# guitar_tuner.net
KiCad netlist of a schematic drawn in Altium Designer
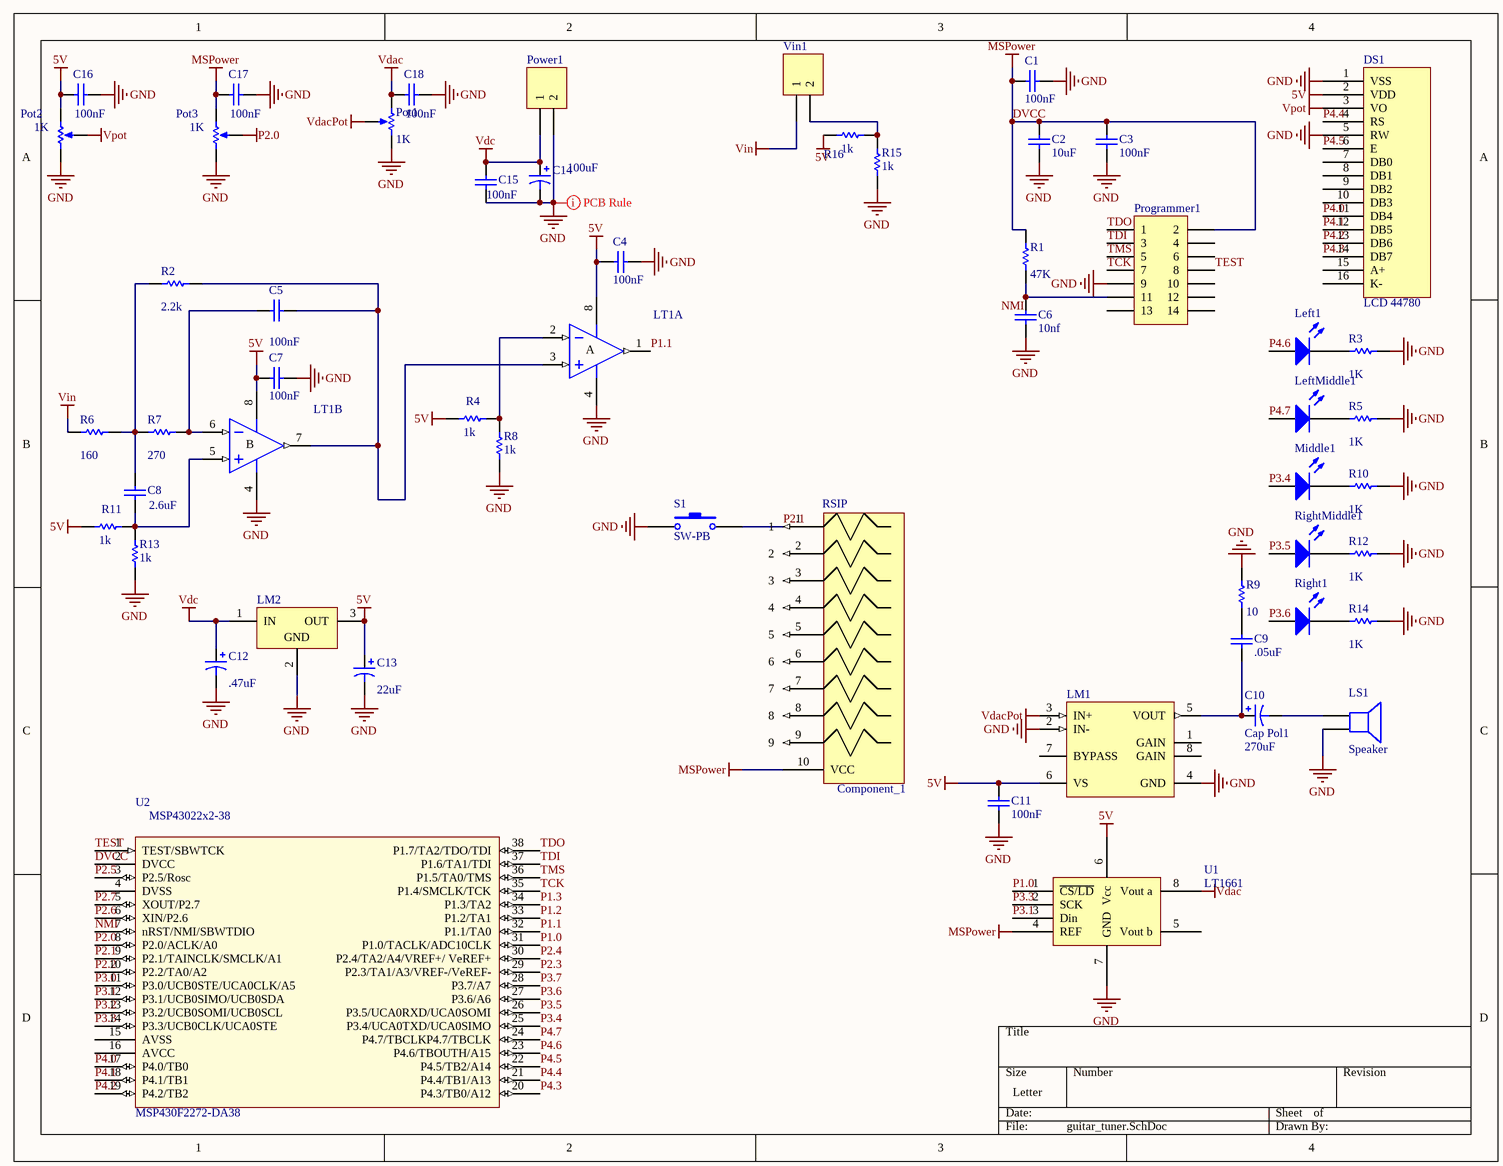
[diagram p0: guitar_tuner.SchDoc]

(export (version "E")
  (design (tool "Eeschema 10.0.6"))
  (components
    (comp (ref "C1")
      (value "100nF")
      (footprint "RAD-0.1")
      (description "Capacitor")
      (fields (field (name "Comment") "Cap") (field (name "PUBLISHER") "Altium Limited"))
      (libsource (lib "Miscellaneous Devices") (part "Cap"))
    )
    (comp (ref "C2")
      (value "10uF")
      (footprint "RAD-0.1")
      (description "Capacitor")
      (fields (field (name "Comment") "Cap") (field (name "PUBLISHER") "Altium Limited"))
      (libsource (lib "Miscellaneous Devices") (part "Cap"))
    )
    (comp (ref "C3")
      (value "100nF")
      (footprint "RAD-0.1")
      (description "Capacitor")
      (fields (field (name "Comment") "Cap") (field (name "PUBLISHER") "Altium Limited"))
      (libsource (lib "Miscellaneous Devices") (part "Cap"))
    )
    (comp (ref "C4")
      (value "100nF")
      (footprint "RAD-0.1")
      (description "Capacitor")
      (fields (field (name "Comment") "Cap") (field (name "PUBLISHER") "Altium Limited"))
      (libsource (lib "Miscellaneous Devices") (part "Cap"))
    )
    (comp (ref "C5")
      (value "100nF")
      (footprint "RAD-0.1")
      (description "Capacitor")
      (fields (field (name "Comment") "Cap") (field (name "PUBLISHER") "Altium Limited"))
      (libsource (lib "Miscellaneous Devices") (part "Cap"))
    )
    (comp (ref "C6")
      (value "10nf")
      (footprint "RAD-0.1")
      (description "Capacitor")
      (fields (field (name "Comment") "Cap") (field (name "PUBLISHER") "Altium Limited"))
      (libsource (lib "Miscellaneous Devices") (part "Cap"))
    )
    (comp (ref "C7")
      (value "100nF")
      (footprint "RAD-0.1")
      (description "Capacitor")
      (fields (field (name "Comment") "Cap") (field (name "PUBLISHER") "Altium Limited"))
      (libsource (lib "Miscellaneous Devices") (part "Cap"))
    )
    (comp (ref "C8")
      (value "2.6uF")
      (footprint "RAD-0.1")
      (description "Capacitor")
      (fields (field (name "Comment") "Cap") (field (name "PUBLISHER") "Altium Limited"))
      (libsource (lib "Miscellaneous Devices") (part "Cap"))
    )
    (comp (ref "C9")
      (value ".05uF")
      (footprint "RAD-0.1")
      (description "Capacitor")
      (fields (field (name "Comment") "Cap") (field (name "PUBLISHER") "Altium Limited"))
      (libsource (lib "Miscellaneous Devices") (part "Cap"))
    )
    (comp (ref "C10")
      (value "Cap Pol1")
      (footprint "CAPR5-4X5")
      (description "Polarized Capacitor (Radial)")
      (fields (field (name "ALTIUM_VALUE") "270uF") (field (name "PUBLISHER") "Altium Limited"))
      (libsource (lib "Miscellaneous Devices") (part "Cap Pol1"))
    )
    (comp (ref "C11")
      (value "100nF")
      (footprint "RAD-0.1")
      (description "Capacitor")
      (fields (field (name "Comment") "Cap") (field (name "PUBLISHER") "Altium Limited"))
      (libsource (lib "Miscellaneous Devices") (part "Cap"))
    )
    (comp (ref "C12")
      (value ".47uF")
      (footprint "CAPR5-4X5")
      (description "Polarized Capacitor (Radial)")
      (fields (field (name "Comment") "Cap Pol1") (field (name "PUBLISHER") "Altium Limited"))
      (libsource (lib "Miscellaneous Devices") (part "Cap Pol1"))
    )
    (comp (ref "C13")
      (value "22uF")
      (footprint "CAPR5-4X5")
      (description "Polarized Capacitor (Radial)")
      (fields (field (name "Comment") "Cap Pol1") (field (name "PUBLISHER") "Altium Limited"))
      (libsource (lib "Miscellaneous Devices") (part "Cap Pol1"))
    )
    (comp (ref "C14")
      (value "100uF")
      (footprint "CAPR5-4X5")
      (description "Polarized Capacitor (Radial)")
      (fields (field (name "Comment") "Cap Pol1") (field (name "PUBLISHER") "Altium Limited"))
      (libsource (lib "Miscellaneous Devices") (part "Cap Pol1"))
    )
    (comp (ref "C15")
      (value "100nF")
      (footprint "RAD-0.1")
      (description "Capacitor")
      (fields (field (name "Comment") "Cap") (field (name "PUBLISHER") "Altium Limited"))
      (libsource (lib "Miscellaneous Devices") (part "Cap"))
    )
    (comp (ref "C16")
      (value "100nF")
      (footprint "RAD-0.1")
      (description "Capacitor")
      (fields (field (name "Comment") "Cap") (field (name "PUBLISHER") "Altium Limited"))
      (libsource (lib "Miscellaneous Devices") (part "Cap"))
    )
    (comp (ref "C17")
      (value "100nF")
      (footprint "RAD-0.1")
      (description "Capacitor")
      (fields (field (name "Comment") "Cap") (field (name "PUBLISHER") "Altium Limited"))
      (libsource (lib "Miscellaneous Devices") (part "Cap"))
    )
    (comp (ref "C18")
      (value "100nF")
      (footprint "RAD-0.1")
      (description "Capacitor")
      (fields (field (name "Comment") "Cap") (field (name "PUBLISHER") "Altium Limited"))
      (libsource (lib "Miscellaneous Devices") (part "Cap"))
    )
    (comp (ref "DS1")
      (value "LCD 44780")
      (footprint "OLED 16x2")
      (libsource (lib "ECE Lib") (part "LCD 44780"))
    )
    (comp (ref "Left1")
      (value "LED1")
      (footprint "LED-1")
      (description "Typical RED GaAs LED")
      (fields (field (name "PUBLISHER") "Altium Limited"))
      (libsource (lib "Miscellaneous Devices") (part "LED1"))
    )
    (comp (ref "LeftMiddle1")
      (value "LED1")
      (footprint "LED-1")
      (description "Typical RED GaAs LED")
      (fields (field (name "PUBLISHER") "Altium Limited"))
      (libsource (lib "Miscellaneous Devices") (part "LED1"))
    )
    (comp (ref "LM1")
      (value "LM386N-1")
      (footprint "N08E")
      (description "Low Voltage Audio Power Amplifier, 8-pin MDIP")
      (fields
        (field (name "MANUFACTURER") "National Semiconductor")
        (field (name "PUBLISHER") "Altium Limited")
      )
      (libsource (lib "NSC Audio") (part "LM386N-1"))
    )
    (comp (ref "LM2")
      (value "LM330KC")
      (footprint "KC03")
      (description "3-Terminal Positive Regulator")
      (fields (field (name "PUBLISHER") "Altium Limited"))
      (libsource (lib "TI Power Mgt Voltage Regulator") (part "LM330KC"))
    )
    (comp (ref "LS1")
      (value "Speaker")
      (footprint "PIN2")
      (description "Loudspeaker")
      (fields (field (name "PUBLISHER") "Altium Limited"))
      (libsource (lib "Miscellaneous Devices") (part "Speaker"))
    )
    (comp (ref "LT1")
      (value "LF353P")
      (footprint "P008")
      (description "Dual Operational Amplifier")
      (fields (field (name "PUBLISHER") "Altium Limited"))
      (libsource (lib "TI Operational Amplifier") (part "LF353P"))
    )
    (comp (ref "Middle1")
      (value "LED1")
      (footprint "LED-1")
      (description "Typical RED GaAs LED")
      (fields (field (name "PUBLISHER") "Altium Limited"))
      (libsource (lib "Miscellaneous Devices") (part "LED1"))
    )
    (comp (ref "Pot1")
      (value "1K")
      (footprint "VR5")
      (description "Potentiometer")
      (fields (field (name "Comment") "RPot") (field (name "PUBLISHER") "Altium Limited"))
      (libsource (lib "Miscellaneous Devices") (part "RPot"))
    )
    (comp (ref "Pot2")
      (value "1K")
      (footprint "VR5")
      (description "Potentiometer")
      (fields (field (name "Comment") "RPot") (field (name "PUBLISHER") "Altium Limited"))
      (libsource (lib "") (part "RPot_1"))
    )
    (comp (ref "Pot3")
      (value "1K")
      (footprint "VR5")
      (description "Potentiometer")
      (fields (field (name "Comment") "RPot") (field (name "PUBLISHER") "Altium Limited"))
      (libsource (lib "") (part "RPot_2"))
    )
    (comp (ref "Power1")
      (value "Power")
      (footprint "HDR1X2")
      (description "Header, 2-Pin")
      (fields (field (name "PUBLISHER") "Altium Limited"))
      (libsource (lib "Miscellaneous Connectors") (part "Header 2"))
    )
    (comp (ref "Programmer1")
      (value "Header 7X2")
      (footprint "HDR2X7")
      (description "Header, 7-Pin, Dual row")
      (fields (field (name "PUBLISHER") "Altium Limited"))
      (libsource (lib "Miscellaneous Connectors") (part "Header 7X2"))
    )
    (comp (ref "R1")
      (value "47K")
      (footprint "AXIAL-0.3")
      (description "Resistor")
      (fields (field (name "Comment") "Res1") (field (name "PUBLISHER") "Altium Limited"))
      (libsource (lib "Miscellaneous Devices") (part "Res1"))
    )
    (comp (ref "R2")
      (value "2.2k")
      (footprint "AXIAL-0.3")
      (description "Resistor")
      (fields (field (name "Comment") "Res1") (field (name "PUBLISHER") "Altium Limited"))
      (libsource (lib "Miscellaneous Devices") (part "Res1"))
    )
    (comp (ref "R3")
      (value "1K")
      (footprint "AXIAL-0.3")
      (description "Resistor")
      (fields (field (name "Comment") "Res1") (field (name "PUBLISHER") "Altium Limited"))
      (libsource (lib "Miscellaneous Devices") (part "Res1"))
    )
    (comp (ref "R4")
      (value "1k")
      (footprint "AXIAL-0.3")
      (description "Resistor")
      (fields (field (name "Comment") "Res1") (field (name "PUBLISHER") "Altium Limited"))
      (libsource (lib "Miscellaneous Devices") (part "Res1"))
    )
    (comp (ref "R5")
      (value "1K")
      (footprint "AXIAL-0.3")
      (description "Resistor")
      (fields (field (name "Comment") "Res1") (field (name "PUBLISHER") "Altium Limited"))
      (libsource (lib "Miscellaneous Devices") (part "Res1"))
    )
    (comp (ref "R6")
      (value "160")
      (footprint "AXIAL-0.3")
      (description "Resistor")
      (fields (field (name "Comment") "Res1") (field (name "PUBLISHER") "Altium Limited"))
      (libsource (lib "Miscellaneous Devices") (part "Res1"))
    )
    (comp (ref "R7")
      (value "270")
      (footprint "AXIAL-0.3")
      (description "Resistor")
      (fields (field (name "Comment") "Res1") (field (name "PUBLISHER") "Altium Limited"))
      (libsource (lib "Miscellaneous Devices") (part "Res1"))
    )
    (comp (ref "R8")
      (value "1k")
      (footprint "AXIAL-0.3")
      (description "Resistor")
      (fields (field (name "Comment") "Res1") (field (name "PUBLISHER") "Altium Limited"))
      (libsource (lib "Miscellaneous Devices") (part "Res1"))
    )
    (comp (ref "R9")
      (value "10")
      (footprint "AXIAL-0.3")
      (description "Resistor")
      (fields (field (name "Comment") "Res1") (field (name "PUBLISHER") "Altium Limited"))
      (libsource (lib "Miscellaneous Devices") (part "Res1"))
    )
    (comp (ref "R10")
      (value "1K")
      (footprint "AXIAL-0.3")
      (description "Resistor")
      (fields (field (name "Comment") "Res1") (field (name "PUBLISHER") "Altium Limited"))
      (libsource (lib "Miscellaneous Devices") (part "Res1"))
    )
    (comp (ref "R11")
      (value "1k")
      (footprint "AXIAL-0.3")
      (description "Resistor")
      (fields (field (name "Comment") "Res1") (field (name "PUBLISHER") "Altium Limited"))
      (libsource (lib "Miscellaneous Devices") (part "Res1"))
    )
    (comp (ref "R12")
      (value "1K")
      (footprint "AXIAL-0.3")
      (description "Resistor")
      (fields (field (name "Comment") "Res1") (field (name "PUBLISHER") "Altium Limited"))
      (libsource (lib "Miscellaneous Devices") (part "Res1"))
    )
    (comp (ref "R13")
      (value "1k")
      (footprint "AXIAL-0.3")
      (description "Resistor")
      (fields (field (name "Comment") "Res1") (field (name "PUBLISHER") "Altium Limited"))
      (libsource (lib "Miscellaneous Devices") (part "Res1"))
    )
    (comp (ref "R14")
      (value "1K")
      (footprint "AXIAL-0.3")
      (description "Resistor")
      (fields (field (name "Comment") "Res1") (field (name "PUBLISHER") "Altium Limited"))
      (libsource (lib "Miscellaneous Devices") (part "Res1"))
    )
    (comp (ref "R15")
      (value "1k")
      (footprint "AXIAL-0.3")
      (description "Resistor")
      (fields (field (name "Comment") "Res1") (field (name "PUBLISHER") "Altium Limited"))
      (libsource (lib "Miscellaneous Devices") (part "Res1"))
    )
    (comp (ref "R16")
      (value "1k")
      (footprint "AXIAL-0.3")
      (description "Resistor")
      (fields (field (name "Comment") "Res1") (field (name "PUBLISHER") "Altium Limited"))
      (libsource (lib "Miscellaneous Devices") (part "Res1"))
    )
    (comp (ref "Right1")
      (value "LED1")
      (footprint "LED-1")
      (description "Typical RED GaAs LED")
      (fields (field (name "PUBLISHER") "Altium Limited"))
      (libsource (lib "Miscellaneous Devices") (part "LED1"))
    )
    (comp (ref "RightMiddle1")
      (value "LED1")
      (footprint "LED-1")
      (description "Typical RED GaAs LED")
      (fields (field (name "PUBLISHER") "Altium Limited"))
      (libsource (lib "Miscellaneous Devices") (part "LED1"))
    )
    (comp (ref "RSIP")
      (value "Component_1")
      (footprint "LTC1661")
      (libsource (lib "Rsip") (part "Component_1"))
    )
    (comp (ref "S1")
      (value "SW-PB")
      (footprint "SW PB")
      (description "DIGIKEY SW400-ND")
      (fields (field (name "PUBLISHER") "Altium Limited"))
      (libsource (lib "ECE Lib") (part "SW-PB"))
    )
    (comp (ref "U1") (value "LT1661") (footprint "DIP-8") (libsource (lib "ECE Lib") (part "LT1661")))
    (comp (ref "U2")
      (value "MSP430F2272-DA38")
      (footprint "DIP38")
      (libsource (lib "ECE Lib") (part "MSP430F22x2-DA38"))
    )
    (comp (ref "Vin1")
      (value "GuitarIn")
      (footprint "HDR1X2")
      (description "Header, 2-Pin")
      (fields (field (name "PUBLISHER") "Altium Limited"))
      (libsource (lib "Miscellaneous Connectors") (part "Header 2"))
    )
  )
  (nets
    (net (code "1") (name "/NMI") (class "Default")
      (node (ref "C6") (pin "1") (pinfunction "1_1") (pintype "passive"))
      (node (ref "Programmer1") (pin "11") (pinfunction "11_11") (pintype "passive"))
      (node (ref "R1") (pin "1") (pinfunction "1_1") (pintype "passive"))
      (node (ref "U2") (pin "7") (pinfunction "nRST/NMI/SBWTDIO_7") (pintype "bidirectional"))
    )
    (net (code "2") (name "/P1.0") (class "Default")
      (node (ref "U1") (pin "1") (pinfunction "~{CS/LD}_1") (pintype "passive"))
      (node (ref "U2") (pin "31") (pinfunction "P1.0/TACLK/ADC10CLK_31") (pintype "bidirectional"))
    )
    (net (code "3") (name "/P1.1") (class "Default")
      (node (ref "LT1") (pin "1") (pinfunction "OUT_1") (pintype "output"))
      (node (ref "U2") (pin "32") (pinfunction "P1.1/TA0_32") (pintype "bidirectional"))
    )
    (net (code "4") (name "/P1.2") (class "Default")
      (node (ref "U2") (pin "33") (pinfunction "P1.2/TA1_33") (pintype "bidirectional"))
    )
    (net (code "5") (name "/P1.3") (class "Default")
      (node (ref "U2") (pin "34") (pinfunction "P1.3/TA2_34") (pintype "bidirectional"))
    )
    (net (code "6") (name "/P2.1") (class "Default")
      (node (ref "S1") (pin "2") (pinfunction "2_2") (pintype "passive"))
      (node (ref "U2") (pin "9") (pinfunction "P2.1/TAINCLK/SMCLK/A1_9") (pintype "bidirectional"))
    )
    (net (code "7") (name "/P2.2") (class "Default")
      (node (ref "U2") (pin "10") (pinfunction "P2.2/TA0/A2_10") (pintype "bidirectional"))
    )
    (net (code "8") (name "/P2.3") (class "Default")
      (node (ref "U2") (pin "29") (pinfunction "P2.3/TA1/A3/VREF-/VeREF-_29") (pintype "bidirectional"))
    )
    (net (code "9") (name "/P2.4") (class "Default")
      (node (ref "U2") (pin "30") (pinfunction "P2.4/TA2/A4/VREF+/_VeREF+_30") (pintype "bidirectional"))
    )
    (net (code "10") (name "/P2.5") (class "Default")
      (node (ref "U2") (pin "3") (pinfunction "P2.5/Rosc_3") (pintype "bidirectional"))
    )
    (net (code "11") (name "/P2.6") (class "Default")
      (node (ref "U2") (pin "6") (pinfunction "XIN/P2.6_6") (pintype "bidirectional"))
    )
    (net (code "12") (name "/P2.7") (class "Default")
      (node (ref "U2") (pin "5") (pinfunction "XOUT/P2.7_5") (pintype "bidirectional"))
    )
    (net (code "13") (name "/P3.0") (class "Default")
      (node (ref "U2") (pin "11") (pinfunction "P3.0/UCB0STE/UCA0CLK/A5_11") (pintype "bidirectional"))
    )
    (net (code "14") (name "/P3.1") (class "Default")
      (node (ref "U1") (pin "3") (pinfunction "Din_3") (pintype "passive"))
      (node (ref "U2") (pin "12") (pinfunction "P3.1/UCB0SIMO/UCB0SDA_12") (pintype "bidirectional"))
    )
    (net (code "15") (name "/P3.2") (class "Default")
      (node (ref "U2") (pin "13") (pinfunction "P3.2/UCB0SOMI/UCB0SCL_13") (pintype "bidirectional"))
    )
    (net (code "16") (name "/P3.3") (class "Default")
      (node (ref "U1") (pin "2") (pinfunction "SCK_2") (pintype "passive"))
      (node (ref "U2") (pin "14") (pinfunction "P3.3/UCB0CLK/UCA0STE_14") (pintype "bidirectional"))
    )
    (net (code "17") (name "/P3.4") (class "Default")
      (node (ref "Middle1") (pin "1") (pinfunction "A_1") (pintype "passive"))
      (node (ref "U2") (pin "25") (pinfunction "P3.4/UCA0TXD/UCA0SIMO_25") (pintype "bidirectional"))
    )
    (net (code "18") (name "/P3.5") (class "Default")
      (node (ref "RightMiddle1") (pin "1") (pinfunction "A_1") (pintype "passive"))
      (node (ref "U2") (pin "26") (pinfunction "P3.5/UCA0RXD/UCA0SOMI_26") (pintype "bidirectional"))
    )
    (net (code "19") (name "/P3.6") (class "Default")
      (node (ref "Right1") (pin "1") (pinfunction "A_1") (pintype "passive"))
      (node (ref "U2") (pin "27") (pinfunction "P3.6/A6_27") (pintype "bidirectional"))
    )
    (net (code "20") (name "/P3.7") (class "Default")
      (node (ref "U2") (pin "28") (pinfunction "P3.7/A7_28") (pintype "bidirectional"))
    )
    (net (code "21") (name "/P4.0") (class "Default")
      (node (ref "DS1") (pin "11") (pinfunction "DB4_11") (pintype "passive"))
      (node (ref "U2") (pin "17") (pinfunction "P4.0/TB0_17") (pintype "bidirectional"))
    )
    (net (code "22") (name "/P4.1") (class "Default")
      (node (ref "DS1") (pin "12") (pinfunction "DB5_12") (pintype "passive"))
      (node (ref "U2") (pin "18") (pinfunction "P4.1/TB1_18") (pintype "bidirectional"))
    )
    (net (code "23") (name "/P4.2") (class "Default")
      (node (ref "DS1") (pin "13") (pinfunction "DB6_13") (pintype "passive"))
      (node (ref "U2") (pin "19") (pinfunction "P4.2/TB2_19") (pintype "bidirectional"))
    )
    (net (code "24") (name "/P4.3") (class "Default")
      (node (ref "DS1") (pin "14") (pinfunction "DB7_14") (pintype "passive"))
      (node (ref "U2") (pin "20") (pinfunction "P4.3/TB0/A12_20") (pintype "bidirectional"))
    )
    (net (code "25") (name "/P4.4") (class "Default")
      (node (ref "DS1") (pin "4") (pinfunction "RS_4") (pintype "passive"))
      (node (ref "U2") (pin "21") (pinfunction "P4.4/TB1/A13_21") (pintype "bidirectional"))
    )
    (net (code "26") (name "/P4.5") (class "Default")
      (node (ref "DS1") (pin "6") (pinfunction "E_6") (pintype "passive"))
      (node (ref "U2") (pin "22") (pinfunction "P4.5/TB2/A14_22") (pintype "bidirectional"))
    )
    (net (code "27") (name "/P4.6") (class "Default")
      (node (ref "Left1") (pin "1") (pinfunction "A_1") (pintype "passive"))
      (node (ref "U2") (pin "23") (pinfunction "P4.6/TBOUTH/A15_23") (pintype "bidirectional"))
    )
    (net (code "28") (name "/P4.7") (class "Default")
      (node (ref "LeftMiddle1") (pin "1") (pinfunction "A_1") (pintype "passive"))
      (node (ref "U2") (pin "24") (pinfunction "P4.7/TBCLKP4.7/TBCLK_24") (pintype "bidirectional"))
    )
    (net (code "29") (name "/TCK") (class "Default")
      (node (ref "Programmer1") (pin "7") (pinfunction "7_7") (pintype "passive"))
      (node (ref "U2") (pin "35") (pinfunction "P1.4/SMCLK/TCK_35") (pintype "bidirectional"))
    )
    (net (code "30") (name "/TDI") (class "Default")
      (node (ref "Programmer1") (pin "3") (pinfunction "3_3") (pintype "passive"))
      (node (ref "U2") (pin "37") (pinfunction "P1.6/TA1/TDI_37") (pintype "bidirectional"))
    )
    (net (code "31") (name "/TDO") (class "Default")
      (node (ref "Programmer1") (pin "1") (pinfunction "1_1") (pintype "passive"))
      (node (ref "U2") (pin "38") (pinfunction "P1.7/TA2/TDO/TDI_38") (pintype "bidirectional"))
    )
    (net (code "32") (name "/TEST") (class "Default")
      (node (ref "Programmer1") (pin "8") (pinfunction "8_8") (pintype "passive"))
      (node (ref "U2") (pin "1") (pinfunction "TEST/SBWTCK_1") (pintype "input"))
    )
    (net (code "33") (name "/TMS") (class "Default")
      (node (ref "Programmer1") (pin "5") (pinfunction "5_5") (pintype "passive"))
      (node (ref "U2") (pin "36") (pinfunction "P1.5/TA0/TMS_36") (pintype "bidirectional"))
    )
    (net (code "34") (name "5V") (class "Default")
      (node (ref "C11") (pin "1") (pinfunction "1_1") (pintype "passive"))
      (node (ref "C13") (pin "1") (pinfunction "1_1") (pintype "passive"))
      (node (ref "C16") (pin "1") (pinfunction "1_1") (pintype "passive"))
      (node (ref "C4") (pin "2") (pinfunction "2_2") (pintype "passive"))
      (node (ref "C7") (pin "1") (pinfunction "1_1") (pintype "passive"))
      (node (ref "DS1") (pin "2") (pinfunction "VDD_2") (pintype "passive"))
      (node (ref "LM1") (pin "6") (pinfunction "VS_6") (pintype "power_in"))
      (node (ref "LM2") (pin "3") (pinfunction "OUT_3") (pintype "power_in"))
      (node (ref "LT1") (pin "8") (pinfunction "V+_8") (pintype "power_in"))
      (node (ref "Pot2") (pin "1") (pinfunction "TOP_1") (pintype "passive"))
      (node (ref "R11") (pin "1") (pinfunction "1_1") (pintype "passive"))
      (node (ref "R16") (pin "1") (pinfunction "1_1") (pintype "passive"))
      (node (ref "R4") (pin "1") (pinfunction "1_1") (pintype "passive"))
      (node (ref "U1") (pin "6") (pinfunction "Vcc_6") (pintype "passive"))
    )
    (net (code "35") (name "GND") (class "Default")
      (node (ref "C1") (pin "1") (pinfunction "1_1") (pintype "passive"))
      (node (ref "C11") (pin "2") (pinfunction "2_2") (pintype "passive"))
      (node (ref "C12") (pin "2") (pinfunction "2_2") (pintype "passive"))
      (node (ref "C13") (pin "2") (pinfunction "2_2") (pintype "passive"))
      (node (ref "C14") (pin "2") (pinfunction "2_2") (pintype "passive"))
      (node (ref "C15") (pin "1") (pinfunction "1_1") (pintype "passive"))
      (node (ref "C16") (pin "2") (pinfunction "2_2") (pintype "passive"))
      (node (ref "C17") (pin "2") (pinfunction "2_2") (pintype "passive"))
      (node (ref "C18") (pin "2") (pinfunction "2_2") (pintype "passive"))
      (node (ref "C2") (pin "2") (pinfunction "2_2") (pintype "passive"))
      (node (ref "C3") (pin "2") (pinfunction "2_2") (pintype "passive"))
      (node (ref "C4") (pin "1") (pinfunction "1_1") (pintype "passive"))
      (node (ref "C6") (pin "2") (pinfunction "2_2") (pintype "passive"))
      (node (ref "C7") (pin "2") (pinfunction "2_2") (pintype "passive"))
      (node (ref "DS1") (pin "1") (pinfunction "VSS_1") (pintype "passive"))
      (node (ref "DS1") (pin "5") (pinfunction "RW_5") (pintype "passive"))
      (node (ref "LM1") (pin "2") (pinfunction "IN-_2") (pintype "input"))
      (node (ref "LM1") (pin "4") (pinfunction "GND_4") (pintype "power_in"))
      (node (ref "LM2") (pin "2") (pinfunction "GND_2") (pintype "power_in"))
      (node (ref "LS1") (pin "2") (pinfunction "2_2") (pintype "passive"))
      (node (ref "LT1") (pin "4") (pinfunction "V-_4") (pintype "power_in"))
      (node (ref "Pot1") (pin "2") (pinfunction "BOT_2") (pintype "passive"))
      (node (ref "Pot2") (pin "3") (pinfunction "TAP_3") (pintype "passive"))
      (node (ref "Pot3") (pin "1") (pinfunction "TOP_1") (pintype "passive"))
      (node (ref "Power1") (pin "2") (pinfunction "2_2") (pintype "passive"))
      (node (ref "Programmer1") (pin "9") (pinfunction "9_9") (pintype "passive"))
      (node (ref "R10") (pin "2") (pinfunction "2_2") (pintype "passive"))
      (node (ref "R12") (pin "2") (pinfunction "2_2") (pintype "passive"))
      (node (ref "R13") (pin "1") (pinfunction "1_1") (pintype "passive"))
      (node (ref "R14") (pin "2") (pinfunction "2_2") (pintype "passive"))
      (node (ref "R15") (pin "1") (pinfunction "1_1") (pintype "passive"))
      (node (ref "R3") (pin "2") (pinfunction "2_2") (pintype "passive"))
      (node (ref "R5") (pin "2") (pinfunction "2_2") (pintype "passive"))
      (node (ref "R8") (pin "1") (pinfunction "1_1") (pintype "passive"))
      (node (ref "R9") (pin "2") (pinfunction "2_2") (pintype "passive"))
      (node (ref "S1") (pin "1") (pinfunction "1_1") (pintype "passive"))
      (node (ref "U1") (pin "7") (pinfunction "GND_7") (pintype "passive"))
    )
    (net (code "36") (name "MSPower") (class "Default")
      (node (ref "C1") (pin "2") (pinfunction "2_2") (pintype "passive"))
      (node (ref "C17") (pin "1") (pinfunction "1_1") (pintype "passive"))
      (node (ref "C2") (pin "1") (pinfunction "1_1") (pintype "passive"))
      (node (ref "C3") (pin "1") (pinfunction "1_1") (pintype "passive"))
      (node (ref "Pot3") (pin "3") (pinfunction "TAP_3") (pintype "passive"))
      (node (ref "Programmer1") (pin "2") (pinfunction "2_2") (pintype "passive"))
      (node (ref "R1") (pin "2") (pinfunction "2_2") (pintype "passive"))
      (node (ref "RSIP") (pin "10") (pinfunction "VCC_10") (pintype "power_in"))
      (node (ref "U1") (pin "4") (pinfunction "REF_4") (pintype "passive"))
      (node (ref "U2") (pin "2") (pinfunction "DVCC_2") (pintype "power_in"))
    )
    (net (code "37") (name "Net-(C8-Pad2)") (class "Default")
      (node (ref "C8") (pin "2") (pinfunction "2_2") (pintype "passive"))
      (node (ref "R2") (pin "1") (pinfunction "1_1") (pintype "passive"))
      (node (ref "R6") (pin "2") (pinfunction "2_2") (pintype "passive"))
      (node (ref "R7") (pin "1") (pinfunction "1_1") (pintype "passive"))
    )
    (net (code "38") (name "Net-(C9-Pad1)") (class "Default")
      (node (ref "C9") (pin "1") (pinfunction "1_1") (pintype "passive"))
      (node (ref "R9") (pin "1") (pinfunction "1_1") (pintype "passive"))
    )
    (net (code "39") (name "Net-(C10-Pad2)") (class "Default")
      (node (ref "C10") (pin "2") (pinfunction "2_2") (pintype "passive"))
      (node (ref "LS1") (pin "1") (pinfunction "1_1") (pintype "passive"))
    )
    (net (code "40") (name "Net-(LM1-VOUT)") (class "Default")
      (node (ref "C10") (pin "1") (pinfunction "1_1") (pintype "passive"))
      (node (ref "C9") (pin "2") (pinfunction "2_2") (pintype "passive"))
      (node (ref "LM1") (pin "5") (pinfunction "VOUT_5") (pintype "output"))
    )
    (net (code "41") (name "Net-(LT1A-IN+)") (class "Default")
      (node (ref "C5") (pin "2") (pinfunction "2_2") (pintype "passive"))
      (node (ref "LT1") (pin "3") (pinfunction "IN+_3") (pintype "input"))
      (node (ref "LT1") (pin "7") (pinfunction "OUT_7") (pintype "output"))
      (node (ref "R2") (pin "2") (pinfunction "2_2") (pintype "passive"))
    )
    (net (code "42") (name "Net-(LT1A-IN-)") (class "Default")
      (node (ref "LT1") (pin "2") (pinfunction "IN-_2") (pintype "input"))
      (node (ref "R4") (pin "2") (pinfunction "2_2") (pintype "passive"))
      (node (ref "R8") (pin "2") (pinfunction "2_2") (pintype "passive"))
    )
    (net (code "43") (name "Net-(LT1B-IN+)") (class "Default")
      (node (ref "C8") (pin "1") (pinfunction "1_1") (pintype "passive"))
      (node (ref "LT1") (pin "5") (pinfunction "IN+_5") (pintype "input"))
      (node (ref "R11") (pin "2") (pinfunction "2_2") (pintype "passive"))
      (node (ref "R13") (pin "2") (pinfunction "2_2") (pintype "passive"))
    )
    (net (code "44") (name "Net-(LT1B-IN-)") (class "Default")
      (node (ref "C5") (pin "1") (pinfunction "1_1") (pintype "passive"))
      (node (ref "LT1") (pin "6") (pinfunction "IN-_6") (pintype "input"))
      (node (ref "R7") (pin "2") (pinfunction "2_2") (pintype "passive"))
    )
    (net (code "45") (name "Net-(Left1-K)") (class "Default")
      (node (ref "Left1") (pin "2") (pinfunction "K_2") (pintype "passive"))
      (node (ref "R3") (pin "1") (pinfunction "1_1") (pintype "passive"))
    )
    (net (code "46") (name "Net-(LeftMiddle1-K)") (class "Default")
      (node (ref "LeftMiddle1") (pin "2") (pinfunction "K_2") (pintype "passive"))
      (node (ref "R5") (pin "1") (pinfunction "1_1") (pintype "passive"))
    )
    (net (code "47") (name "Net-(Middle1-K)") (class "Default")
      (node (ref "Middle1") (pin "2") (pinfunction "K_2") (pintype "passive"))
      (node (ref "R10") (pin "1") (pinfunction "1_1") (pintype "passive"))
    )
    (net (code "48") (name "Net-(R15-Pad2)") (class "Default")
      (node (ref "R15") (pin "2") (pinfunction "2_2") (pintype "passive"))
      (node (ref "R16") (pin "2") (pinfunction "2_2") (pintype "passive"))
      (node (ref "Vin1") (pin "2") (pinfunction "2_2") (pintype "passive"))
    )
    (net (code "49") (name "Net-(Right1-K)") (class "Default")
      (node (ref "R14") (pin "1") (pinfunction "1_1") (pintype "passive"))
      (node (ref "Right1") (pin "2") (pinfunction "K_2") (pintype "passive"))
    )
    (net (code "50") (name "Net-(RightMiddle1-K)") (class "Default")
      (node (ref "R12") (pin "1") (pinfunction "1_1") (pintype "passive"))
      (node (ref "RightMiddle1") (pin "2") (pinfunction "K_2") (pintype "passive"))
    )
    (net (code "51") (name "P2.0") (class "Default")
      (node (ref "Pot3") (pin "2") (pinfunction "BOT_2") (pintype "passive"))
      (node (ref "U2") (pin "8") (pinfunction "P2.0/ACLK/A0_8") (pintype "bidirectional"))
    )
    (net (code "52") (name "Vdac") (class "Default")
      (node (ref "C18") (pin "1") (pinfunction "1_1") (pintype "passive"))
      (node (ref "Pot1") (pin "1") (pinfunction "TOP_1") (pintype "passive"))
      (node (ref "U1") (pin "8") (pinfunction "Vout_a_8") (pintype "passive"))
    )
    (net (code "53") (name "VdacPot") (class "Default")
      (node (ref "LM1") (pin "3") (pinfunction "IN+_3") (pintype "input"))
      (node (ref "Pot1") (pin "3") (pinfunction "TAP_3") (pintype "passive"))
    )
    (net (code "54") (name "Vdc") (class "Default")
      (node (ref "C12") (pin "1") (pinfunction "1_1") (pintype "passive"))
      (node (ref "C14") (pin "1") (pinfunction "1_1") (pintype "passive"))
      (node (ref "C15") (pin "2") (pinfunction "2_2") (pintype "passive"))
      (node (ref "LM2") (pin "1") (pinfunction "IN_1") (pintype "power_in"))
      (node (ref "Power1") (pin "1") (pinfunction "1_1") (pintype "passive"))
    )
    (net (code "55") (name "Vin") (class "Default")
      (node (ref "R6") (pin "1") (pinfunction "1_1") (pintype "passive"))
      (node (ref "Vin1") (pin "1") (pinfunction "1_1") (pintype "passive"))
    )
    (net (code "56") (name "Vpot") (class "Default")
      (node (ref "DS1") (pin "3") (pinfunction "VO_3") (pintype "passive"))
      (node (ref "Pot2") (pin "2") (pinfunction "BOT_2") (pintype "passive"))
    )
    (net (code "57") (name "unconnected-(DS1-A+-Pad15)") (class "Default")
      (node (ref "DS1") (pin "15") (pinfunction "A+_15") (pintype "passive"))
    )
    (net (code "58") (name "unconnected-(DS1-DB0-Pad7)") (class "Default")
      (node (ref "DS1") (pin "7") (pinfunction "DB0_7") (pintype "passive"))
    )
    (net (code "59") (name "unconnected-(DS1-DB1-Pad8)") (class "Default")
      (node (ref "DS1") (pin "8") (pinfunction "DB1_8") (pintype "passive"))
    )
    (net (code "60") (name "unconnected-(DS1-DB2-Pad9)") (class "Default")
      (node (ref "DS1") (pin "9") (pinfunction "DB2_9") (pintype "passive"))
    )
    (net (code "61") (name "unconnected-(DS1-DB3-Pad10)") (class "Default")
      (node (ref "DS1") (pin "10") (pinfunction "DB3_10") (pintype "passive"))
    )
    (net (code "62") (name "unconnected-(DS1-K--Pad16)") (class "Default")
      (node (ref "DS1") (pin "16") (pinfunction "K-_16") (pintype "passive"))
    )
    (net (code "63") (name "unconnected-(LM1-BYPASS-Pad7)") (class "Default")
      (node (ref "LM1") (pin "7") (pinfunction "BYPASS_7") (pintype "passive"))
    )
    (net (code "64") (name "unconnected-(LM1-GAIN-Pad1)") (class "Default")
      (node (ref "LM1") (pin "1") (pinfunction "GAIN_1") (pintype "passive"))
    )
    (net (code "65") (name "unconnected-(LM1-GAIN-Pad8)") (class "Default")
      (node (ref "LM1") (pin "8") (pinfunction "GAIN_8") (pintype "passive"))
    )
    (net (code "66") (name "unconnected-(Programmer1-Pad4)") (class "Default")
      (node (ref "Programmer1") (pin "4") (pinfunction "4_4") (pintype "passive"))
    )
    (net (code "67") (name "unconnected-(Programmer1-Pad6)") (class "Default")
      (node (ref "Programmer1") (pin "6") (pinfunction "6_6") (pintype "passive"))
    )
    (net (code "68") (name "unconnected-(Programmer1-Pad10)") (class "Default")
      (node (ref "Programmer1") (pin "10") (pinfunction "10_10") (pintype "passive"))
    )
    (net (code "69") (name "unconnected-(Programmer1-Pad12)") (class "Default")
      (node (ref "Programmer1") (pin "12") (pinfunction "12_12") (pintype "passive"))
    )
    (net (code "70") (name "unconnected-(Programmer1-Pad13)") (class "Default")
      (node (ref "Programmer1") (pin "13") (pinfunction "13_13") (pintype "passive"))
    )
    (net (code "71") (name "unconnected-(Programmer1-Pad14)") (class "Default")
      (node (ref "Programmer1") (pin "14") (pinfunction "14_14") (pintype "passive"))
    )
    (net (code "72") (name "unconnected-(RSIP-Pad1)") (class "Default")
      (node (ref "RSIP") (pin "1") (pinfunction "1_1") (pintype "input"))
    )
    (net (code "73") (name "unconnected-(RSIP-Pad2)") (class "Default")
      (node (ref "RSIP") (pin "2") (pinfunction "2_2") (pintype "input"))
    )
    (net (code "74") (name "unconnected-(RSIP-Pad3)") (class "Default")
      (node (ref "RSIP") (pin "3") (pinfunction "3_3") (pintype "input"))
    )
    (net (code "75") (name "unconnected-(RSIP-Pad4)") (class "Default")
      (node (ref "RSIP") (pin "4") (pinfunction "4_4") (pintype "input"))
    )
    (net (code "76") (name "unconnected-(RSIP-Pad5)") (class "Default")
      (node (ref "RSIP") (pin "5") (pinfunction "5_5") (pintype "input"))
    )
    (net (code "77") (name "unconnected-(RSIP-Pad6)") (class "Default")
      (node (ref "RSIP") (pin "6") (pinfunction "6_6") (pintype "input"))
    )
    (net (code "78") (name "unconnected-(RSIP-Pad7)") (class "Default")
      (node (ref "RSIP") (pin "7") (pinfunction "7_7") (pintype "input"))
    )
    (net (code "79") (name "unconnected-(RSIP-Pad8)") (class "Default")
      (node (ref "RSIP") (pin "8") (pinfunction "8_8") (pintype "input"))
    )
    (net (code "80") (name "unconnected-(RSIP-Pad9)") (class "Default")
      (node (ref "RSIP") (pin "9") (pinfunction "9_9") (pintype "input"))
    )
    (net (code "81") (name "unconnected-(U1-Vout_b-Pad5)") (class "Default")
      (node (ref "U1") (pin "5") (pinfunction "Vout_b_5") (pintype "passive"))
    )
    (net (code "82") (name "unconnected-(U2-AVCC-Pad16)") (class "Default")
      (node (ref "U2") (pin "16") (pinfunction "AVCC_16") (pintype "power_in"))
    )
    (net (code "83") (name "unconnected-(U2-AVSS-Pad15)") (class "Default")
      (node (ref "U2") (pin "15") (pinfunction "AVSS_15") (pintype "power_in"))
    )
    (net (code "84") (name "unconnected-(U2-DVSS-Pad4)") (class "Default")
      (node (ref "U2") (pin "4") (pinfunction "DVSS_4") (pintype "power_in"))
    )
  )
)
